# Sensors.net
KiCad netlist of a schematic drawn in Altium Designer
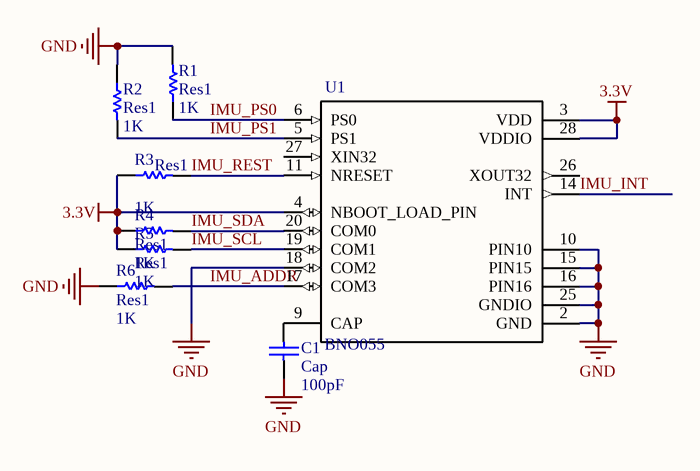
[diagram p0: Sensors.SchDoc]

(export (version "E")
  (design (tool "Eeschema 10.0.6"))
  (components
    (comp (ref "C1")
      (value "Cap")
      (footprint "RAD-0.3")
      (description "Capacitor")
      (fields (field (name "ALTIUM_VALUE") "100pF") (field (name "PUBLISHER") "Altium Limited"))
      (libsource (lib "Miscellaneous Devices") (part "Cap"))
    )
    (comp (ref "R1")
      (value "Res1")
      (footprint "AXIAL-0.3")
      (description "Resistor")
      (fields (field (name "ALTIUM_VALUE") "1K") (field (name "PUBLISHER") "Altium Limited"))
      (libsource (lib "Miscellaneous Devices") (part "Res1"))
    )
    (comp (ref "R2")
      (value "Res1")
      (footprint "AXIAL-0.3")
      (description "Resistor")
      (fields (field (name "ALTIUM_VALUE") "1K") (field (name "PUBLISHER") "Altium Limited"))
      (libsource (lib "Miscellaneous Devices") (part "Res1"))
    )
    (comp (ref "R3")
      (value "Res1")
      (footprint "AXIAL-0.3")
      (description "Resistor")
      (fields (field (name "ALTIUM_VALUE") "1K") (field (name "PUBLISHER") "Altium Limited"))
      (libsource (lib "Miscellaneous Devices") (part "Res1"))
    )
    (comp (ref "R4")
      (value "Res1")
      (footprint "AXIAL-0.3")
      (description "Resistor")
      (fields (field (name "ALTIUM_VALUE") "1K") (field (name "PUBLISHER") "Altium Limited"))
      (libsource (lib "Miscellaneous Devices") (part "Res1"))
    )
    (comp (ref "R5")
      (value "Res1")
      (footprint "AXIAL-0.3")
      (description "Resistor")
      (fields (field (name "ALTIUM_VALUE") "1K") (field (name "PUBLISHER") "Altium Limited"))
      (libsource (lib "Miscellaneous Devices") (part "Res1"))
    )
    (comp (ref "R6")
      (value "Res1")
      (footprint "AXIAL-0.3")
      (description "Resistor")
      (fields (field (name "ALTIUM_VALUE") "1K") (field (name "PUBLISHER") "Altium Limited"))
      (libsource (lib "Miscellaneous Devices") (part "Res1"))
    )
    (comp (ref "U1")
      (value "BNO055")
      (footprint "*LGA28R50P4X10_380X520X100")
      (description "BNO055 9-axis Absolute Orientation Sensor _ SiP _ w/Sensors and Sensor Fusion")
      (fields (field (name "MF") "Bosch"))
      (libsource (lib "BNO055") (part "BNO055"))
    )
  )
  (nets
    (net (code "1") (name "/IMU_ADDR") (class "Default")
      (node (ref "R6") (pin "2") (pinfunction "2_2") (pintype "passive"))
      (node (ref "U1") (pin "17") (pinfunction "COM3_17") (pintype "bidirectional"))
    )
    (net (code "2") (name "/IMU_INT") (class "Default")
      (node (ref "U1") (pin "14") (pinfunction "INT_14") (pintype "output"))
    )
    (net (code "3") (name "/IMU_PS0") (class "Default")
      (node (ref "R1") (pin "1") (pinfunction "1_1") (pintype "passive"))
      (node (ref "U1") (pin "6") (pinfunction "PS0_6") (pintype "input"))
    )
    (net (code "4") (name "/IMU_PS1") (class "Default")
      (node (ref "R2") (pin "2") (pinfunction "2_2") (pintype "passive"))
      (node (ref "U1") (pin "5") (pinfunction "PS1_5") (pintype "input"))
    )
    (net (code "5") (name "/IMU_REST") (class "Default")
      (node (ref "R3") (pin "2") (pinfunction "2_2") (pintype "passive"))
      (node (ref "U1") (pin "11") (pinfunction "NRESET_11") (pintype "input"))
    )
    (net (code "6") (name "/IMU_SCL") (class "Default")
      (node (ref "R5") (pin "2") (pinfunction "2_2") (pintype "passive"))
      (node (ref "U1") (pin "19") (pinfunction "COM1_19") (pintype "bidirectional"))
    )
    (net (code "7") (name "/IMU_SDA") (class "Default")
      (node (ref "R4") (pin "2") (pinfunction "2_2") (pintype "passive"))
      (node (ref "U1") (pin "20") (pinfunction "COM0_20") (pintype "bidirectional"))
    )
    (net (code "8") (name "3.3V") (class "Default")
      (node (ref "R3") (pin "1") (pinfunction "1_1") (pintype "passive"))
      (node (ref "R4") (pin "1") (pinfunction "1_1") (pintype "passive"))
      (node (ref "R5") (pin "1") (pinfunction "1_1") (pintype "passive"))
      (node (ref "U1") (pin "28") (pinfunction "VDDIO_28") (pintype "power_in"))
      (node (ref "U1") (pin "3") (pinfunction "VDD_3") (pintype "power_in"))
      (node (ref "U1") (pin "4") (pinfunction "NBOOT_LOAD_PIN_4") (pintype "bidirectional"))
    )
    (net (code "9") (name "GND") (class "Default")
      (node (ref "C1") (pin "1") (pinfunction "1_1") (pintype "passive"))
      (node (ref "R1") (pin "2") (pinfunction "2_2") (pintype "passive"))
      (node (ref "R2") (pin "1") (pinfunction "1_1") (pintype "passive"))
      (node (ref "R6") (pin "1") (pinfunction "1_1") (pintype "passive"))
      (node (ref "U1") (pin "10") (pinfunction "PIN10_10") (pintype "power_in"))
      (node (ref "U1") (pin "15") (pinfunction "PIN15_15") (pintype "power_in"))
      (node (ref "U1") (pin "16") (pinfunction "PIN16_16") (pintype "power_in"))
      (node (ref "U1") (pin "18") (pinfunction "COM2_18") (pintype "bidirectional"))
      (node (ref "U1") (pin "2") (pinfunction "GND_2") (pintype "power_in"))
      (node (ref "U1") (pin "25") (pinfunction "GNDIO_25") (pintype "power_in"))
    )
    (net (code "10") (name "Net-(U1-CAP)") (class "Default")
      (node (ref "C1") (pin "2") (pinfunction "2_2") (pintype "passive"))
      (node (ref "U1") (pin "9") (pinfunction "CAP_9") (pintype "passive"))
    )
    (net (code "11") (name "unconnected-(U1-XIN32-Pad27)") (class "Default")
      (node (ref "U1") (pin "27") (pinfunction "XIN32_27") (pintype "input"))
    )
    (net (code "12") (name "unconnected-(U1-XOUT32-Pad26)") (class "Default")
      (node (ref "U1") (pin "26") (pinfunction "XOUT32_26") (pintype "output"))
    )
  )
)
